# RxBrd_v2.net
KiCad netlist of a schematic drawn in EAGLE
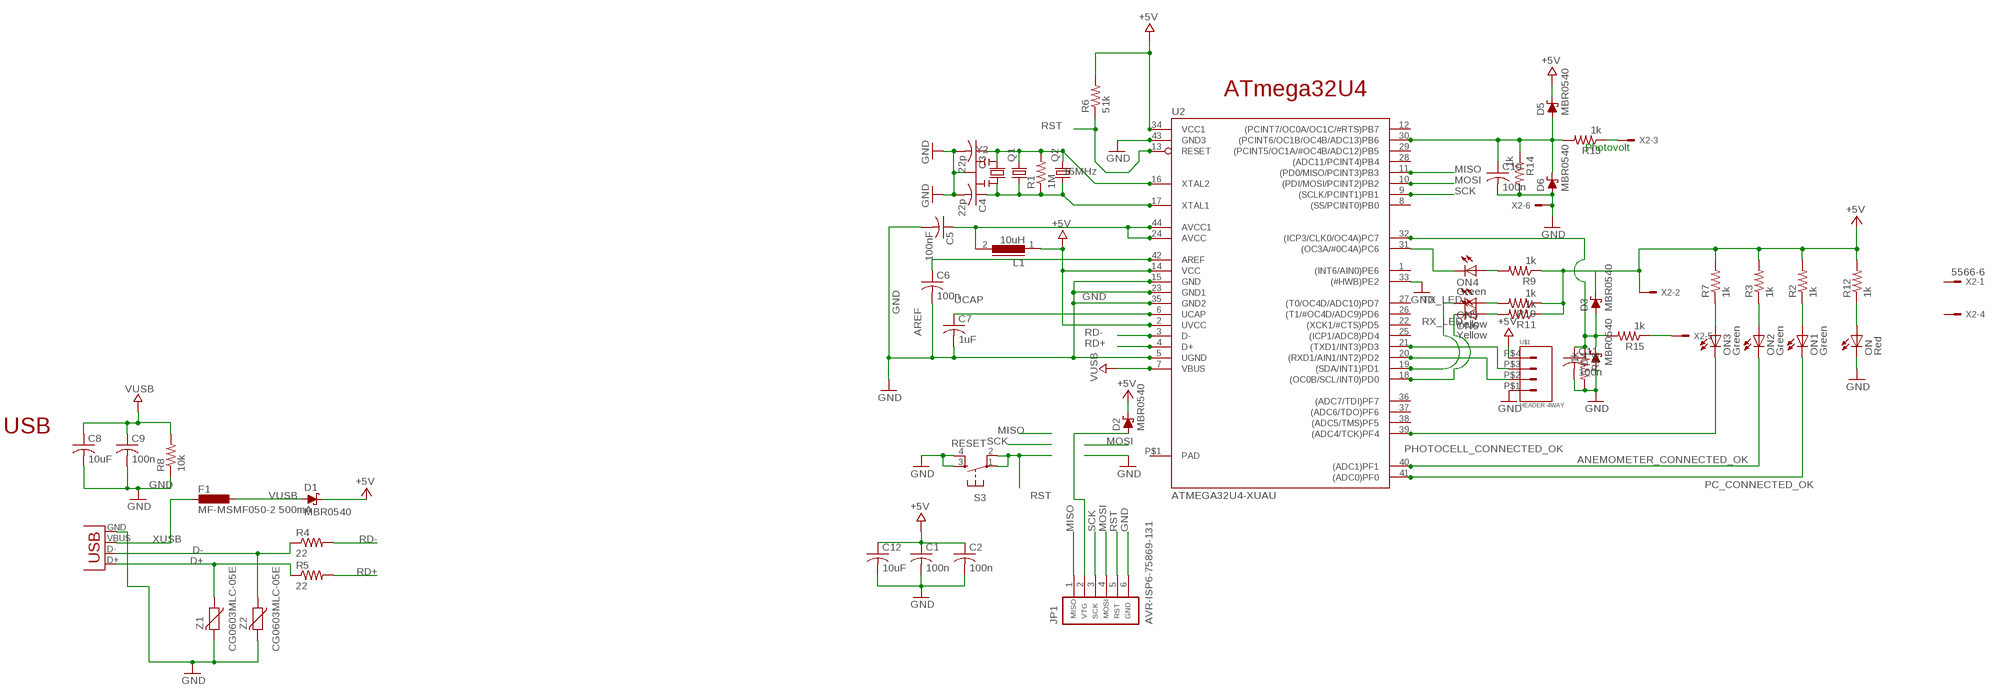
[diagram p0: schematic, sheet 1]

(export (version "E")
  (design (tool "Eeschema 10.0.6"))
  (components
    (comp (ref "C1")
      (value "100n")
      (footprint "eagle-import:C0805")
      (libsource (lib "eagle-import") (part "C-USC0805"))
    )
    (comp (ref "C2")
      (value "100n")
      (footprint "eagle-import:C0805")
      (libsource (lib "eagle-import") (part "C-USC0805"))
    )
    (comp (ref "C3")
      (value "22p")
      (footprint "eagle-import:C0805")
      (libsource (lib "eagle-import") (part "C-USC0805"))
    )
    (comp (ref "C4")
      (value "22p")
      (footprint "eagle-import:C0805")
      (libsource (lib "eagle-import") (part "C-USC0805"))
    )
    (comp (ref "C5")
      (value "100nF")
      (footprint "eagle-import:C0805")
      (libsource (lib "eagle-import") (part "C-USC0805"))
    )
    (comp (ref "C6")
      (value "100n")
      (footprint "eagle-import:C0805")
      (libsource (lib "eagle-import") (part "C-USC0805"))
    )
    (comp (ref "C7")
      (value "1uF")
      (footprint "eagle-import:C0805")
      (libsource (lib "eagle-import") (part "C-USC0805"))
    )
    (comp (ref "C8")
      (value "10uF")
      (footprint "eagle-import:C0805")
      (libsource (lib "eagle-import") (part "C-USC0805"))
    )
    (comp (ref "C9")
      (value "100n")
      (footprint "eagle-import:C0805")
      (libsource (lib "eagle-import") (part "C-USC0805"))
    )
    (comp (ref "C10")
      (value "100n")
      (footprint "eagle-import:C0805")
      (libsource (lib "eagle-import") (part "C-USC0805"))
    )
    (comp (ref "C11")
      (value "100n")
      (footprint "eagle-import:C0805")
      (libsource (lib "eagle-import") (part "C-USC0805"))
    )
    (comp (ref "C12")
      (value "10uF")
      (footprint "eagle-import:C0805")
      (libsource (lib "eagle-import") (part "C-USC0805"))
    )
    (comp (ref "D1")
      (value "MBR0540")
      (footprint "eagle-import:SOD123@2")
      (libsource (lib "eagle-import") (part "MBR0540"))
    )
    (comp (ref "D2")
      (value "MBR0540")
      (footprint "eagle-import:SOD123@2")
      (libsource (lib "eagle-import") (part "MBR0540"))
    )
    (comp (ref "D3")
      (value "MBR0540")
      (footprint "eagle-import:SOD123@2")
      (libsource (lib "eagle-import") (part "MBR0540"))
    )
    (comp (ref "D4")
      (value "MBR0540")
      (footprint "eagle-import:SOD123@2")
      (libsource (lib "eagle-import") (part "MBR0540"))
    )
    (comp (ref "D5")
      (value "MBR0540")
      (footprint "eagle-import:SOD123@2")
      (libsource (lib "eagle-import") (part "MBR0540"))
    )
    (comp (ref "D6")
      (value "MBR0540")
      (footprint "eagle-import:SOD123@2")
      (libsource (lib "eagle-import") (part "MBR0540"))
    )
    (comp (ref "F1")
      (value "MF-MSMF050-2 500mA")
      (footprint "eagle-import:L1812")
      (libsource (lib "eagle-import") (part "L-EUL1812"))
    )
    (comp (ref "JP1")
      (value "AVR-ISP6-75869-131")
      (footprint "eagle-import:HDR-75869-131")
      (libsource (lib "eagle-import") (part "AVR-ISP6-75869-131"))
    )
    (comp (ref "L1")
      (value "10uH")
      (footprint "eagle-import:MMICC7")
      (libsource (lib "eagle-import") (part "MMICC7"))
    )
    (comp (ref "ON")
      (value "Red")
      (footprint "eagle-import:CHIPLED_0805")
      (libsource (lib "eagle-import") (part "LEDCHIPLED_0805"))
    )
    (comp (ref "ON1")
      (value "Green")
      (footprint "eagle-import:CHIPLED_0805")
      (libsource (lib "eagle-import") (part "LEDCHIPLED_0805"))
    )
    (comp (ref "ON2")
      (value "Green")
      (footprint "eagle-import:CHIPLED_0805")
      (libsource (lib "eagle-import") (part "LEDCHIPLED_0805"))
    )
    (comp (ref "ON3")
      (value "Green")
      (footprint "eagle-import:CHIPLED_0805")
      (libsource (lib "eagle-import") (part "LEDCHIPLED_0805"))
    )
    (comp (ref "ON4")
      (value "Green")
      (footprint "eagle-import:CHIPLED_0805")
      (libsource (lib "eagle-import") (part "LEDCHIPLED_0805"))
    )
    (comp (ref "ON5")
      (value "Yellow")
      (footprint "eagle-import:CHIPLED_0805")
      (libsource (lib "eagle-import") (part "LEDCHIPLED_0805"))
    )
    (comp (ref "ON6")
      (value "Yellow")
      (footprint "eagle-import:CHIPLED_0805")
      (libsource (lib "eagle-import") (part "LEDCHIPLED_0805"))
    )
    (comp (ref "Q1")
      (value "CRYSTALHC49UP")
      (footprint "eagle-import:HC49UP")
      (libsource (lib "eagle-import") (part "CRYSTALHC49UP"))
    )
    (comp (ref "Q2")
      (value "CRYSTALHC49S")
      (footprint "eagle-import:HC49_S")
      (libsource (lib "eagle-import") (part "CRYSTALHC49S"))
    )
    (comp (ref "R1")
      (value "1M")
      (footprint "eagle-import:R0805")
      (libsource (lib "eagle-import") (part "R-US_R0805"))
    )
    (comp (ref "R2")
      (value "1k")
      (footprint "eagle-import:R0805")
      (libsource (lib "eagle-import") (part "R-US_R0805"))
    )
    (comp (ref "R3")
      (value "1k")
      (footprint "eagle-import:R0805")
      (libsource (lib "eagle-import") (part "R-US_R0805"))
    )
    (comp (ref "R4")
      (value "22")
      (footprint "eagle-import:R0805")
      (libsource (lib "eagle-import") (part "R-US_R0805"))
    )
    (comp (ref "R5")
      (value "22")
      (footprint "eagle-import:R0805")
      (libsource (lib "eagle-import") (part "R-US_R0805"))
    )
    (comp (ref "R6")
      (value "51k")
      (footprint "eagle-import:R0805")
      (libsource (lib "eagle-import") (part "R-US_R0805"))
    )
    (comp (ref "R7")
      (value "1k")
      (footprint "eagle-import:R0805")
      (libsource (lib "eagle-import") (part "R-US_R0805"))
    )
    (comp (ref "R8")
      (value "10k")
      (footprint "eagle-import:R0805")
      (libsource (lib "eagle-import") (part "R-US_R0805"))
    )
    (comp (ref "R9")
      (value "1k")
      (footprint "eagle-import:R0805")
      (libsource (lib "eagle-import") (part "R-US_R0805"))
    )
    (comp (ref "R10")
      (value "1k")
      (footprint "eagle-import:R0805")
      (libsource (lib "eagle-import") (part "R-US_R0805"))
    )
    (comp (ref "R11")
      (value "1k")
      (footprint "eagle-import:R0805")
      (libsource (lib "eagle-import") (part "R-US_R0805"))
    )
    (comp (ref "R12")
      (value "1k")
      (footprint "eagle-import:R0805")
      (libsource (lib "eagle-import") (part "R-US_R0805"))
    )
    (comp (ref "R13")
      (value "1k")
      (footprint "eagle-import:R0805")
      (libsource (lib "eagle-import") (part "R-US_R0805"))
    )
    (comp (ref "R14")
      (value "1k")
      (footprint "eagle-import:R0805")
      (libsource (lib "eagle-import") (part "R-US_R0805"))
    )
    (comp (ref "R15")
      (value "1k")
      (footprint "eagle-import:R0805")
      (libsource (lib "eagle-import") (part "R-US_R0805"))
    )
    (comp (ref "R16")
      (value "1k")
      (footprint "eagle-import:R0805")
      (libsource (lib "eagle-import") (part "R-US_R0805"))
    )
    (comp (ref "S3")
      (value "RESET")
      (footprint "eagle-import:TACTILE_SWITCH_SMD")
      (libsource (lib "eagle-import") (part "TAC_SWITCHSMD"))
    )
    (comp (ref "U$1")
      (value "HEADER-4WAY")
      (footprint "eagle-import:1744426-4")
      (libsource (lib "eagle-import") (part "HEADER-4WAY"))
    )
    (comp (ref "U2")
      (value "ATMEGA32U4-XUAU")
      (footprint "eagle-import:TQFP44-PAD")
      (libsource (lib "eagle-import") (part "ATMEGA32U4-XUAU"))
    )
    (comp (ref "X1")
      (value "USBPTH")
      (footprint "eagle-import:USB-B-PTH")
      (libsource (lib "eagle-import") (part "USBPTH"))
    )
    (comp (ref "X2")
      (value "5566-6")
      (footprint "eagle-import:5566-6")
      (fields (field (name "MPN") "95566-61002"))
      (libsource (lib "eagle-import") (part "5566-6"))
    )
    (comp (ref "Y2")
      (value "16MHz")
      (footprint "eagle-import:RESONATOR")
      (libsource (lib "eagle-import") (part "RESONATORMU"))
    )
    (comp (ref "Z1")
      (value "CG0603MLC-05E")
      (footprint "eagle-import:CT_CN0603")
      (libsource (lib "eagle-import") (part "VARISTORCN0603"))
    )
    (comp (ref "Z2")
      (value "CG0603MLC-05E")
      (footprint "eagle-import:CT_CN0603")
      (libsource (lib "eagle-import") (part "VARISTORCN0603"))
    )
  )
  (nets
    (net (code "1") (name "+5V") (class "Default")
      (node (ref "C1") (pin "1") (pinfunction "1_1") (pintype "passive"))
      (node (ref "C12") (pin "1") (pinfunction "1_1") (pintype "passive"))
      (node (ref "C2") (pin "1") (pinfunction "1_1") (pintype "passive"))
      (node (ref "D1") (pin "C") (pinfunction "C_C") (pintype "passive"))
      (node (ref "D2") (pin "C") (pinfunction "C_C") (pintype "passive"))
      (node (ref "D3") (pin "C") (pinfunction "C_C") (pintype "passive"))
      (node (ref "D5") (pin "C") (pinfunction "C_C") (pintype "passive"))
      (node (ref "L1") (pin "1") (pinfunction "1_1") (pintype "passive"))
      (node (ref "R10") (pin "1") (pinfunction "1_1") (pintype "passive"))
      (node (ref "R11") (pin "1") (pinfunction "1_1") (pintype "passive"))
      (node (ref "R12") (pin "2") (pinfunction "2_2") (pintype "passive"))
      (node (ref "R2") (pin "2") (pinfunction "2_2") (pintype "passive"))
      (node (ref "R3") (pin "2") (pinfunction "2_2") (pintype "passive"))
      (node (ref "R6") (pin "2") (pinfunction "2_2") (pintype "passive"))
      (node (ref "R7") (pin "2") (pinfunction "2_2") (pintype "passive"))
      (node (ref "R9") (pin "1") (pinfunction "1_1") (pintype "passive"))
      (node (ref "U$1") (pin "P$4") (pinfunction "P$4_P$4") (pintype "passive"))
      (node (ref "U2") (pin "14") (pinfunction "VCC_14") (pintype "power_in"))
      (node (ref "U2") (pin "2") (pinfunction "UVCC_2") (pintype "power_in"))
      (node (ref "U2") (pin "34") (pinfunction "VCC1_34") (pintype "power_in"))
      (node (ref "X2") (pin "2") (pinfunction "S_2") (pintype "passive"))
    )
    (net (code "2") (name "/ANEMOMETER_CONNECTED_OK") (class "Default")
      (node (ref "ON2") (pin "C") (pinfunction "C_C") (pintype "passive"))
      (node (ref "U2") (pin "40") (pinfunction "(ADC1)PF1_40") (pintype "bidirectional"))
    )
    (net (code "3") (name "/AREF") (class "Default")
      (node (ref "C6") (pin "1") (pinfunction "1_1") (pintype "passive"))
      (node (ref "U2") (pin "42") (pinfunction "AREF_42") (pintype "power_in"))
    )
    (net (code "4") (name "/D+") (class "Default")
      (node (ref "R5") (pin "1") (pinfunction "1_1") (pintype "passive"))
      (node (ref "X1") (pin "D+") (pinfunction "D+_D+") (pintype "bidirectional"))
      (node (ref "Z1") (pin "1") (pinfunction "1_1") (pintype "passive"))
    )
    (net (code "5") (name "/D-") (class "Default")
      (node (ref "R4") (pin "1") (pinfunction "1_1") (pintype "passive"))
      (node (ref "X1") (pin "D-") (pinfunction "D-_D-") (pintype "bidirectional"))
      (node (ref "Z2") (pin "1") (pinfunction "1_1") (pintype "passive"))
    )
    (net (code "6") (name "/MISO") (class "Default")
      (node (ref "JP1") (pin "1") (pinfunction "1_1") (pintype "passive"))
      (node (ref "U2") (pin "11") (pinfunction "(PD0/MISO/PCINT3)PB3_11") (pintype "bidirectional"))
    )
    (net (code "7") (name "/MOSI") (class "Default")
      (node (ref "JP1") (pin "4") (pinfunction "4_4") (pintype "passive"))
      (node (ref "U2") (pin "10") (pinfunction "(PDI/MOSI/PCINT2)PB2_10") (pintype "bidirectional"))
    )
    (net (code "8") (name "/PAD") (class "Default")
      (node (ref "U2") (pin "P$1") (pinfunction "PAD_P$1") (pintype "power_in"))
    )
    (net (code "9") (name "/PC_CONNECTED_OK") (class "Default")
      (node (ref "ON1") (pin "C") (pinfunction "C_C") (pintype "passive"))
      (node (ref "U2") (pin "41") (pinfunction "(ADC0)PF0_41") (pintype "bidirectional"))
    )
    (net (code "10") (name "/PHOTOCELL_CONNECTED_OK") (class "Default")
      (node (ref "ON3") (pin "C") (pinfunction "C_C") (pintype "passive"))
      (node (ref "U2") (pin "39") (pinfunction "(ADC4/TCK)PF4_39") (pintype "bidirectional"))
    )
    (net (code "11") (name "/RD+") (class "Default")
      (node (ref "R5") (pin "2") (pinfunction "2_2") (pintype "passive"))
      (node (ref "U2") (pin "4") (pinfunction "D+_4") (pintype "bidirectional"))
    )
    (net (code "12") (name "/RD-") (class "Default")
      (node (ref "R4") (pin "2") (pinfunction "2_2") (pintype "passive"))
      (node (ref "U2") (pin "3") (pinfunction "D-_3") (pintype "bidirectional"))
    )
    (net (code "13") (name "/RST") (class "Default")
      (node (ref "JP1") (pin "5") (pinfunction "5_5") (pintype "passive"))
      (node (ref "R6") (pin "1") (pinfunction "1_1") (pintype "passive"))
      (node (ref "S3") (pin "1") (pinfunction "1_1") (pintype "passive"))
      (node (ref "S3") (pin "2") (pinfunction "2_2") (pintype "passive"))
      (node (ref "U2") (pin "13") (pinfunction "RESET_13") (pintype "input"))
    )
    (net (code "14") (name "/RX_LED") (class "Default")
      (node (ref "ON6") (pin "C") (pinfunction "C_C") (pintype "passive"))
      (node (ref "U2") (pin "18") (pinfunction "(OC0B/SCL/INT0)PD0_18") (pintype "bidirectional"))
    )
    (net (code "15") (name "/SCK") (class "Default")
      (node (ref "JP1") (pin "3") (pinfunction "3_3") (pintype "passive"))
      (node (ref "U2") (pin "9") (pinfunction "(SCLK/PCINT1)PB1_9") (pintype "bidirectional"))
    )
    (net (code "16") (name "/TX_LED") (class "Default")
      (node (ref "ON5") (pin "C") (pinfunction "C_C") (pintype "passive"))
      (node (ref "U2") (pin "19") (pinfunction "(SDA/INT1)PD1_19") (pintype "bidirectional"))
    )
    (net (code "17") (name "/UCAP") (class "Default")
      (node (ref "C7") (pin "1") (pinfunction "1_1") (pintype "passive"))
      (node (ref "U2") (pin "6") (pinfunction "UCAP_6") (pintype "passive"))
    )
    (net (code "18") (name "/XUSB") (class "Default")
      (node (ref "F1") (pin "2") (pinfunction "2_2") (pintype "passive"))
      (node (ref "X1") (pin "VBUS") (pinfunction "VBUS_VBUS") (pintype "bidirectional"))
    )
    (net (code "19") (name "GND") (class "Default")
      (node (ref "C1") (pin "2") (pinfunction "2_2") (pintype "passive"))
      (node (ref "C10") (pin "2") (pinfunction "2_2") (pintype "passive"))
      (node (ref "C11") (pin "2") (pinfunction "2_2") (pintype "passive"))
      (node (ref "C12") (pin "2") (pinfunction "2_2") (pintype "passive"))
      (node (ref "C2") (pin "2") (pinfunction "2_2") (pintype "passive"))
      (node (ref "C3") (pin "2") (pinfunction "2_2") (pintype "passive"))
      (node (ref "C4") (pin "2") (pinfunction "2_2") (pintype "passive"))
      (node (ref "C5") (pin "2") (pinfunction "2_2") (pintype "passive"))
      (node (ref "C6") (pin "2") (pinfunction "2_2") (pintype "passive"))
      (node (ref "C7") (pin "2") (pinfunction "2_2") (pintype "passive"))
      (node (ref "C8") (pin "2") (pinfunction "2_2") (pintype "passive"))
      (node (ref "C9") (pin "2") (pinfunction "2_2") (pintype "passive"))
      (node (ref "D4") (pin "A") (pinfunction "A_A") (pintype "passive"))
      (node (ref "D6") (pin "A") (pinfunction "A_A") (pintype "passive"))
      (node (ref "JP1") (pin "6") (pinfunction "6_6") (pintype "passive"))
      (node (ref "ON") (pin "C") (pinfunction "C_C") (pintype "passive"))
      (node (ref "R14") (pin "2") (pinfunction "2_2") (pintype "passive"))
      (node (ref "R16") (pin "2") (pinfunction "2_2") (pintype "passive"))
      (node (ref "R8") (pin "1") (pinfunction "1_1") (pintype "passive"))
      (node (ref "S3") (pin "3") (pinfunction "3_3") (pintype "passive"))
      (node (ref "S3") (pin "4") (pinfunction "4_4") (pintype "passive"))
      (node (ref "U$1") (pin "P$1") (pinfunction "P$1_P$1") (pintype "passive"))
      (node (ref "U2") (pin "15") (pinfunction "GND_15") (pintype "power_in"))
      (node (ref "U2") (pin "23") (pinfunction "GND1_23") (pintype "power_in"))
      (node (ref "U2") (pin "33") (pinfunction "(#HWB)PE2_33") (pintype "bidirectional"))
      (node (ref "U2") (pin "35") (pinfunction "GND2_35") (pintype "power_in"))
      (node (ref "U2") (pin "43") (pinfunction "GND3_43") (pintype "power_in"))
      (node (ref "U2") (pin "5") (pinfunction "UGND_5") (pintype "power_in"))
      (node (ref "X1") (pin "GND") (pinfunction "GND_GND") (pintype "bidirectional"))
      (node (ref "X2") (pin "6") (pinfunction "S_6") (pintype "passive"))
      (node (ref "Y2") (pin "2") (pinfunction "2_2") (pintype "passive"))
      (node (ref "Z1") (pin "2") (pinfunction "2_2") (pintype "passive"))
      (node (ref "Z2") (pin "2") (pinfunction "2_2") (pintype "passive"))
    )
    (net (code "20") (name "Net-(D2-PadA)") (class "Default")
      (node (ref "D2") (pin "A") (pinfunction "A_A") (pintype "passive"))
      (node (ref "JP1") (pin "2") (pinfunction "2_2") (pintype "passive"))
    )
    (net (code "21") (name "Net-(ON-PadA)") (class "Default")
      (node (ref "ON") (pin "A") (pinfunction "A_A") (pintype "passive"))
      (node (ref "R12") (pin "1") (pinfunction "1_1") (pintype "passive"))
    )
    (net (code "22") (name "Net-(ON1-PadA)") (class "Default")
      (node (ref "ON1") (pin "A") (pinfunction "A_A") (pintype "passive"))
      (node (ref "R2") (pin "1") (pinfunction "1_1") (pintype "passive"))
    )
    (net (code "23") (name "Net-(ON2-PadA)") (class "Default")
      (node (ref "ON2") (pin "A") (pinfunction "A_A") (pintype "passive"))
      (node (ref "R3") (pin "1") (pinfunction "1_1") (pintype "passive"))
    )
    (net (code "24") (name "Net-(ON3-PadA)") (class "Default")
      (node (ref "ON3") (pin "A") (pinfunction "A_A") (pintype "passive"))
      (node (ref "R7") (pin "1") (pinfunction "1_1") (pintype "passive"))
    )
    (net (code "25") (name "Net-(ON4-PadA)") (class "Default")
      (node (ref "ON4") (pin "A") (pinfunction "A_A") (pintype "passive"))
      (node (ref "R9") (pin "2") (pinfunction "2_2") (pintype "passive"))
    )
    (net (code "26") (name "Net-(ON5-PadA)") (class "Default")
      (node (ref "ON5") (pin "A") (pinfunction "A_A") (pintype "passive"))
      (node (ref "R10") (pin "2") (pinfunction "2_2") (pintype "passive"))
    )
    (net (code "27") (name "Net-(ON6-PadA)") (class "Default")
      (node (ref "ON6") (pin "A") (pinfunction "A_A") (pintype "passive"))
      (node (ref "R11") (pin "2") (pinfunction "2_2") (pintype "passive"))
    )
    (net (code "28") (name "Net-(U2-(ICP3{slash}CLK0{slash}OC4A)PC7)") (class "Default")
      (node (ref "C11") (pin "1") (pinfunction "1_1") (pintype "passive"))
      (node (ref "D3") (pin "A") (pinfunction "A_A") (pintype "passive"))
      (node (ref "D4") (pin "C") (pinfunction "C_C") (pintype "passive"))
      (node (ref "R15") (pin "2") (pinfunction "2_2") (pintype "passive"))
      (node (ref "R16") (pin "1") (pinfunction "1_1") (pintype "passive"))
      (node (ref "U2") (pin "32") (pinfunction "(ICP3/CLK0/OC4A)PC7_32") (pintype "bidirectional"))
    )
    (net (code "29") (name "Net-(U2-(OC3A{slash}#0C4A)PC6)") (class "Default")
      (node (ref "ON4") (pin "C") (pinfunction "C_C") (pintype "passive"))
      (node (ref "U2") (pin "31") (pinfunction "(OC3A/#0C4A)PC6_31") (pintype "bidirectional"))
    )
    (net (code "30") (name "Net-(U2-(PCINT6{slash}OC1B{slash}OC4B{slash}ADC13)PB6)") (class "Default")
      (node (ref "C10") (pin "1") (pinfunction "1_1") (pintype "passive"))
      (node (ref "D5") (pin "A") (pinfunction "A_A") (pintype "passive"))
      (node (ref "D6") (pin "C") (pinfunction "C_C") (pintype "passive"))
      (node (ref "R13") (pin "2") (pinfunction "2_2") (pintype "passive"))
      (node (ref "R14") (pin "1") (pinfunction "1_1") (pintype "passive"))
      (node (ref "U2") (pin "30") (pinfunction "(PCINT6/OC1B/OC4B/ADC13)PB6_30") (pintype "bidirectional"))
    )
    (net (code "31") (name "Net-(U2-(RXD1{slash}AIN1{slash}INT2)PD2)") (class "Default")
      (node (ref "U$1") (pin "P$2") (pinfunction "P$2_P$2") (pintype "passive"))
      (node (ref "U2") (pin "20") (pinfunction "(RXD1/AIN1/INT2)PD2_20") (pintype "bidirectional"))
    )
    (net (code "32") (name "Net-(U2-(TXD1{slash}INT3)PD3)") (class "Default")
      (node (ref "U$1") (pin "P$3") (pinfunction "P$3_P$3") (pintype "passive"))
      (node (ref "U2") (pin "21") (pinfunction "(TXD1/INT3)PD3_21") (pintype "bidirectional"))
    )
    (net (code "33") (name "Net-(U2-AVCC)") (class "Default")
      (node (ref "C5") (pin "1") (pinfunction "1_1") (pintype "passive"))
      (node (ref "L1") (pin "2") (pinfunction "2_2") (pintype "passive"))
      (node (ref "U2") (pin "24") (pinfunction "AVCC_24") (pintype "power_in"))
      (node (ref "U2") (pin "44") (pinfunction "AVCC1_44") (pintype "power_in"))
    )
    (net (code "34") (name "Net-(U2-XTAL1)") (class "Default")
      (node (ref "C4") (pin "1") (pinfunction "1_1") (pintype "passive"))
      (node (ref "Q1") (pin "1") (pinfunction "1_1") (pintype "passive"))
      (node (ref "Q2") (pin "1") (pinfunction "1_1") (pintype "passive"))
      (node (ref "R1") (pin "1") (pinfunction "1_1") (pintype "passive"))
      (node (ref "U2") (pin "17") (pinfunction "XTAL1_17") (pintype "bidirectional"))
      (node (ref "Y2") (pin "3") (pinfunction "3_3") (pintype "passive"))
    )
    (net (code "35") (name "Net-(U2-XTAL2)") (class "Default")
      (node (ref "C3") (pin "1") (pinfunction "1_1") (pintype "passive"))
      (node (ref "Q1") (pin "2") (pinfunction "2_2") (pintype "passive"))
      (node (ref "Q2") (pin "2") (pinfunction "2_2") (pintype "passive"))
      (node (ref "R1") (pin "2") (pinfunction "2_2") (pintype "passive"))
      (node (ref "U2") (pin "16") (pinfunction "XTAL2_16") (pintype "bidirectional"))
      (node (ref "Y2") (pin "1") (pinfunction "1_1") (pintype "passive"))
    )
    (net (code "36") (name "Net-(X2C-S)") (class "Default")
      (node (ref "R13") (pin "1") (pinfunction "1_1") (pintype "passive"))
      (node (ref "X2") (pin "3") (pinfunction "S_3") (pintype "passive"))
    )
    (net (code "37") (name "Net-(X2E-S)") (class "Default")
      (node (ref "R15") (pin "1") (pinfunction "1_1") (pintype "passive"))
      (node (ref "X2") (pin "5") (pinfunction "S_5") (pintype "passive"))
    )
    (net (code "38") (name "VUSB") (class "Default")
      (node (ref "C8") (pin "1") (pinfunction "1_1") (pintype "passive"))
      (node (ref "C9") (pin "1") (pinfunction "1_1") (pintype "passive"))
      (node (ref "D1") (pin "A") (pinfunction "A_A") (pintype "passive"))
      (node (ref "F1") (pin "1") (pinfunction "1_1") (pintype "passive"))
      (node (ref "R8") (pin "2") (pinfunction "2_2") (pintype "passive"))
      (node (ref "U2") (pin "7") (pinfunction "VBUS_7") (pintype "input"))
    )
    (net (code "39") (name "unconnected-(U2-(ADC5{slash}TMS)PF5-Pad38)") (class "Default")
      (node (ref "U2") (pin "38") (pinfunction "(ADC5/TMS)PF5_38") (pintype "bidirectional"))
    )
    (net (code "40") (name "unconnected-(U2-(ADC6{slash}TDO)PF6-Pad37)") (class "Default")
      (node (ref "U2") (pin "37") (pinfunction "(ADC6/TDO)PF6_37") (pintype "bidirectional"))
    )
    (net (code "41") (name "unconnected-(U2-(ADC7{slash}TDI)PF7-Pad36)") (class "Default")
      (node (ref "U2") (pin "36") (pinfunction "(ADC7/TDI)PF7_36") (pintype "bidirectional"))
    )
    (net (code "42") (name "unconnected-(U2-(ADC11{slash}PCINT4)PB4-Pad28)") (class "Default")
      (node (ref "U2") (pin "28") (pinfunction "(ADC11/PCINT4)PB4_28") (pintype "bidirectional"))
    )
    (net (code "43") (name "unconnected-(U2-(ICP1{slash}ADC8)PD4-Pad25)") (class "Default")
      (node (ref "U2") (pin "25") (pinfunction "(ICP1/ADC8)PD4_25") (pintype "bidirectional"))
    )
    (net (code "44") (name "unconnected-(U2-(INT6{slash}AIN0)PE6-Pad1)") (class "Default")
      (node (ref "U2") (pin "1") (pinfunction "(INT6/AIN0)PE6_1") (pintype "bidirectional"))
    )
    (net (code "45") (name "unconnected-(U2-(PCINT5{slash}OC1A{slash}#OC4B{slash}ADC12)PB5-Pad29)") (class "Default")
      (node (ref "U2") (pin "29") (pinfunction "(PCINT5/OC1A/#OC4B/ADC12)PB5_29") (pintype "bidirectional"))
    )
    (net (code "46") (name "unconnected-(U2-(PCINT7{slash}OC0A{slash}OC1C{slash}#RTS)PB7-Pad12)") (class "Default")
      (node (ref "U2") (pin "12") (pinfunction "(PCINT7/OC0A/OC1C/#RTS)PB7_12") (pintype "bidirectional"))
    )
    (net (code "47") (name "unconnected-(U2-(SS{slash}PCINT0)PB0-Pad8)") (class "Default")
      (node (ref "U2") (pin "8") (pinfunction "(SS/PCINT0)PB0_8") (pintype "bidirectional"))
    )
    (net (code "48") (name "unconnected-(U2-(T0{slash}OC4D{slash}ADC10)PD7-Pad27)") (class "Default")
      (node (ref "U2") (pin "27") (pinfunction "(T0/OC4D/ADC10)PD7_27") (pintype "bidirectional"))
    )
    (net (code "49") (name "unconnected-(U2-(T1{slash}#OC4D{slash}ADC9)PD6-Pad26)") (class "Default")
      (node (ref "U2") (pin "26") (pinfunction "(T1/#OC4D/ADC9)PD6_26") (pintype "bidirectional"))
    )
    (net (code "50") (name "unconnected-(U2-(XCK1{slash}#CTS)PD5-Pad22)") (class "Default")
      (node (ref "U2") (pin "22") (pinfunction "(XCK1/#CTS)PD5_22") (pintype "bidirectional"))
    )
    (net (code "51") (name "unconnected-(X2A-S-Pad1)") (class "Default")
      (node (ref "X2") (pin "1") (pinfunction "S_1") (pintype "passive"))
    )
    (net (code "52") (name "unconnected-(X2D-S-Pad4)") (class "Default")
      (node (ref "X2") (pin "4") (pinfunction "S_4") (pintype "passive"))
    )
  )
)
